# BMS-TEMPSTRIP-LEFT-S00.net
KiCad netlist of a schematic drawn in Altium Designer
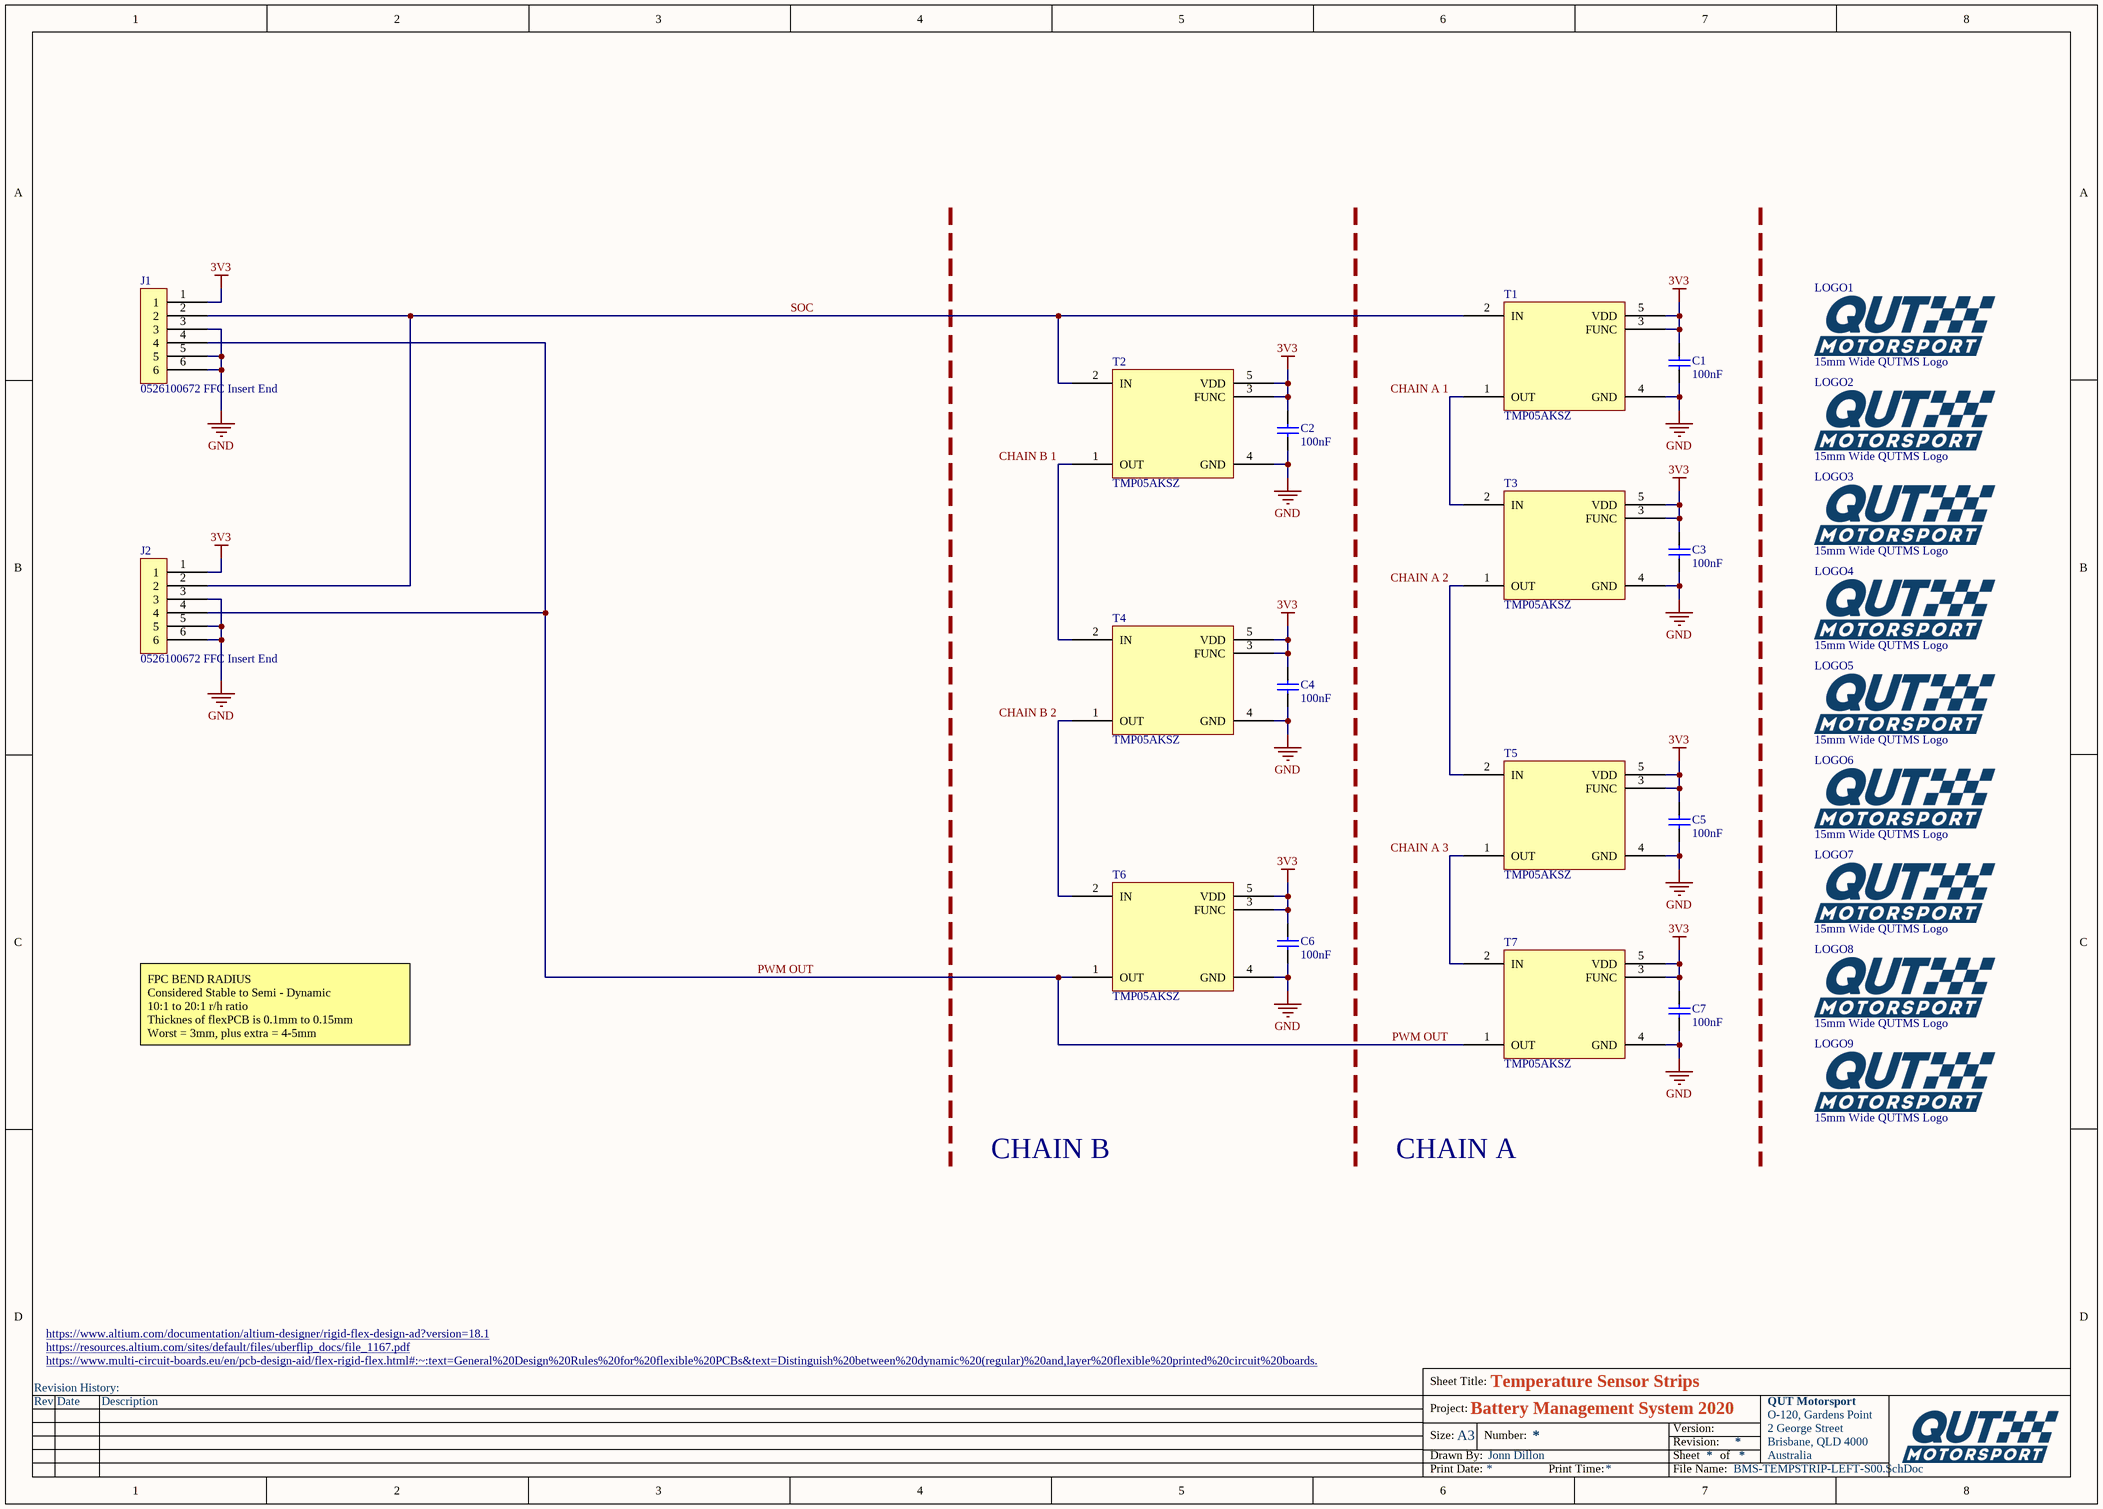
[diagram p0: BMS-TEMPSTRIP-LEFT-S00.SchDoc]

(export (version "E")
  (design (tool "Eeschema 10.0.6"))
  (components
    (comp (ref "C1")
      (value "100nF")
      (footprint "Cap_Ceramic_0603")
      (description "Capacitor, Ceramic, SMD, 100nF, 50V, 5%, X7R, 0603")
      (libsource (lib "StandardCapacitors") (part "100nF 50V 5% X7R 0603"))
    )
    (comp (ref "C2")
      (value "100nF")
      (footprint "Cap_Ceramic_0603")
      (description "Capacitor, Ceramic, SMD, 100nF, 50V, 5%, X7R, 0603")
      (libsource (lib "StandardCapacitors") (part "100nF 50V 5% X7R 0603"))
    )
    (comp (ref "C3")
      (value "100nF")
      (footprint "Cap_Ceramic_0603")
      (description "Capacitor, Ceramic, SMD, 100nF, 50V, 5%, X7R, 0603")
      (libsource (lib "StandardCapacitors") (part "100nF 50V 5% X7R 0603"))
    )
    (comp (ref "C4")
      (value "100nF")
      (footprint "Cap_Ceramic_0603")
      (description "Capacitor, Ceramic, SMD, 100nF, 50V, 5%, X7R, 0603")
      (libsource (lib "StandardCapacitors") (part "100nF 50V 5% X7R 0603"))
    )
    (comp (ref "C5")
      (value "100nF")
      (footprint "Cap_Ceramic_0603")
      (description "Capacitor, Ceramic, SMD, 100nF, 50V, 5%, X7R, 0603")
      (libsource (lib "StandardCapacitors") (part "100nF 50V 5% X7R 0603"))
    )
    (comp (ref "C6")
      (value "100nF")
      (footprint "Cap_Ceramic_0603")
      (description "Capacitor, Ceramic, SMD, 100nF, 50V, 5%, X7R, 0603")
      (libsource (lib "StandardCapacitors") (part "100nF 50V 5% X7R 0603"))
    )
    (comp (ref "C7")
      (value "100nF")
      (footprint "Cap_Ceramic_0603")
      (description "Capacitor, Ceramic, SMD, 100nF, 50V, 5%, X7R, 0603")
      (libsource (lib "StandardCapacitors") (part "100nF 50V 5% X7R 0603"))
    )
    (comp (ref "J1")
      (value "0526100672 FFC Insert End")
      (footprint "0526100672 FFC Insert End")
      (libsource (lib "BMS-TEMPSTRIP") (part "0526100672 FFC Insert End"))
    )
    (comp (ref "J2")
      (value "0526100672 FFC Insert End")
      (footprint "0526100672 FFC Insert End")
      (libsource (lib "BMS-TEMPSTRIP") (part "0526100672 FFC Insert End"))
    )
    (comp (ref "LOGO1")
      (value "15mm Wide QUTMS Logo")
      (footprint "QUTMS LOGO 15MM")
      (libsource (lib "QUTMS_PCBLibrary") (part "QUTMS Logo 15mm"))
    )
    (comp (ref "LOGO2")
      (value "15mm Wide QUTMS Logo")
      (footprint "QUTMS LOGO 15MM")
      (libsource (lib "QUTMS_PCBLibrary") (part "QUTMS Logo 15mm"))
    )
    (comp (ref "LOGO3")
      (value "15mm Wide QUTMS Logo")
      (footprint "QUTMS LOGO 15MM")
      (libsource (lib "QUTMS_PCBLibrary") (part "QUTMS Logo 15mm"))
    )
    (comp (ref "LOGO4")
      (value "15mm Wide QUTMS Logo")
      (footprint "QUTMS LOGO 15MM")
      (libsource (lib "QUTMS_PCBLibrary") (part "QUTMS Logo 15mm"))
    )
    (comp (ref "LOGO5")
      (value "15mm Wide QUTMS Logo")
      (footprint "QUTMS LOGO 15MM")
      (libsource (lib "QUTMS_PCBLibrary") (part "QUTMS Logo 15mm"))
    )
    (comp (ref "LOGO6")
      (value "15mm Wide QUTMS Logo")
      (footprint "QUTMS LOGO 15MM")
      (libsource (lib "QUTMS_PCBLibrary") (part "QUTMS Logo 15mm"))
    )
    (comp (ref "LOGO7")
      (value "15mm Wide QUTMS Logo")
      (footprint "QUTMS LOGO 15MM")
      (libsource (lib "QUTMS_PCBLibrary") (part "QUTMS Logo 15mm"))
    )
    (comp (ref "LOGO8")
      (value "15mm Wide QUTMS Logo")
      (footprint "QUTMS LOGO 15MM")
      (libsource (lib "QUTMS_PCBLibrary") (part "QUTMS Logo 15mm"))
    )
    (comp (ref "LOGO9")
      (value "15mm Wide QUTMS Logo")
      (footprint "QUTMS LOGO 15MM")
      (libsource (lib "QUTMS_PCBLibrary") (part "QUTMS Logo 15mm"))
    )
    (comp (ref "T1")
      (value "TMP05AKSZ")
      (footprint "SC-70 (KS-5)")
      (description "Temperature Sensor, SMD, 3.3V, 2%, SOT-353")
      (libsource (lib "BMS-TEMPSTRIP") (part "TMP05AKSZ"))
    )
    (comp (ref "T2")
      (value "TMP05AKSZ")
      (footprint "SC-70 (KS-5)")
      (description "Temperature Sensor, SMD, 3.3V, 2%, SOT-353")
      (libsource (lib "BMS-TEMPSTRIP") (part "TMP05AKSZ"))
    )
    (comp (ref "T3")
      (value "TMP05AKSZ")
      (footprint "SC-70 (KS-5)")
      (description "Temperature Sensor, SMD, 3.3V, 2%, SOT-353")
      (libsource (lib "BMS-TEMPSTRIP") (part "TMP05AKSZ"))
    )
    (comp (ref "T4")
      (value "TMP05AKSZ")
      (footprint "SC-70 (KS-5)")
      (description "Temperature Sensor, SMD, 3.3V, 2%, SOT-353")
      (libsource (lib "BMS-TEMPSTRIP") (part "TMP05AKSZ"))
    )
    (comp (ref "T5")
      (value "TMP05AKSZ")
      (footprint "SC-70 (KS-5)")
      (description "Temperature Sensor, SMD, 3.3V, 2%, SOT-353")
      (libsource (lib "BMS-TEMPSTRIP") (part "TMP05AKSZ"))
    )
    (comp (ref "T6")
      (value "TMP05AKSZ")
      (footprint "SC-70 (KS-5)")
      (description "Temperature Sensor, SMD, 3.3V, 2%, SOT-353")
      (libsource (lib "BMS-TEMPSTRIP") (part "TMP05AKSZ"))
    )
    (comp (ref "T7")
      (value "TMP05AKSZ")
      (footprint "SC-70 (KS-5)")
      (description "Temperature Sensor, SMD, 3.3V, 2%, SOT-353")
      (libsource (lib "BMS-TEMPSTRIP") (part "TMP05AKSZ"))
    )
  )
  (nets
    (net (code "1") (name "/CHAIN A 1") (class "Default")
      (node (ref "T1") (pin "1") (pinfunction "OUT_1") (pintype "passive"))
      (node (ref "T3") (pin "2") (pinfunction "IN_2") (pintype "passive"))
    )
    (net (code "2") (name "/CHAIN A 2") (class "Default")
      (node (ref "T3") (pin "1") (pinfunction "OUT_1") (pintype "passive"))
      (node (ref "T5") (pin "2") (pinfunction "IN_2") (pintype "passive"))
    )
    (net (code "3") (name "/CHAIN A 3") (class "Default")
      (node (ref "T5") (pin "1") (pinfunction "OUT_1") (pintype "passive"))
      (node (ref "T7") (pin "2") (pinfunction "IN_2") (pintype "passive"))
    )
    (net (code "4") (name "/CHAIN B 1") (class "Default")
      (node (ref "T2") (pin "1") (pinfunction "OUT_1") (pintype "passive"))
      (node (ref "T4") (pin "2") (pinfunction "IN_2") (pintype "passive"))
    )
    (net (code "5") (name "/CHAIN B 2") (class "Default")
      (node (ref "T4") (pin "1") (pinfunction "OUT_1") (pintype "passive"))
      (node (ref "T6") (pin "2") (pinfunction "IN_2") (pintype "passive"))
    )
    (net (code "6") (name "/PWM OUT") (class "Default")
      (node (ref "J1") (pin "4") (pinfunction "4_4") (pintype "passive"))
      (node (ref "J2") (pin "4") (pinfunction "4_4") (pintype "passive"))
      (node (ref "T6") (pin "1") (pinfunction "OUT_1") (pintype "passive"))
      (node (ref "T7") (pin "1") (pinfunction "OUT_1") (pintype "passive"))
    )
    (net (code "7") (name "/SOC") (class "Default")
      (node (ref "J1") (pin "2") (pinfunction "2_2") (pintype "passive"))
      (node (ref "J2") (pin "2") (pinfunction "2_2") (pintype "passive"))
      (node (ref "T1") (pin "2") (pinfunction "IN_2") (pintype "passive"))
      (node (ref "T2") (pin "2") (pinfunction "IN_2") (pintype "passive"))
    )
    (net (code "8") (name "3V3") (class "Default")
      (node (ref "C1") (pin "1") (pinfunction "1_1") (pintype "passive"))
      (node (ref "C2") (pin "1") (pinfunction "1_1") (pintype "passive"))
      (node (ref "C3") (pin "1") (pinfunction "1_1") (pintype "passive"))
      (node (ref "C4") (pin "1") (pinfunction "1_1") (pintype "passive"))
      (node (ref "C5") (pin "1") (pinfunction "1_1") (pintype "passive"))
      (node (ref "C6") (pin "1") (pinfunction "1_1") (pintype "passive"))
      (node (ref "C7") (pin "1") (pinfunction "1_1") (pintype "passive"))
      (node (ref "J1") (pin "1") (pinfunction "1_1") (pintype "passive"))
      (node (ref "J2") (pin "1") (pinfunction "1_1") (pintype "passive"))
      (node (ref "T1") (pin "3") (pinfunction "FUNC_3") (pintype "passive"))
      (node (ref "T1") (pin "5") (pinfunction "VDD_5") (pintype "passive"))
      (node (ref "T2") (pin "3") (pinfunction "FUNC_3") (pintype "passive"))
      (node (ref "T2") (pin "5") (pinfunction "VDD_5") (pintype "passive"))
      (node (ref "T3") (pin "3") (pinfunction "FUNC_3") (pintype "passive"))
      (node (ref "T3") (pin "5") (pinfunction "VDD_5") (pintype "passive"))
      (node (ref "T4") (pin "3") (pinfunction "FUNC_3") (pintype "passive"))
      (node (ref "T4") (pin "5") (pinfunction "VDD_5") (pintype "passive"))
      (node (ref "T5") (pin "3") (pinfunction "FUNC_3") (pintype "passive"))
      (node (ref "T5") (pin "5") (pinfunction "VDD_5") (pintype "passive"))
      (node (ref "T6") (pin "3") (pinfunction "FUNC_3") (pintype "passive"))
      (node (ref "T6") (pin "5") (pinfunction "VDD_5") (pintype "passive"))
      (node (ref "T7") (pin "3") (pinfunction "FUNC_3") (pintype "passive"))
      (node (ref "T7") (pin "5") (pinfunction "VDD_5") (pintype "passive"))
    )
    (net (code "9") (name "GND") (class "Default")
      (node (ref "C1") (pin "2") (pinfunction "2_2") (pintype "passive"))
      (node (ref "C2") (pin "2") (pinfunction "2_2") (pintype "passive"))
      (node (ref "C3") (pin "2") (pinfunction "2_2") (pintype "passive"))
      (node (ref "C4") (pin "2") (pinfunction "2_2") (pintype "passive"))
      (node (ref "C5") (pin "2") (pinfunction "2_2") (pintype "passive"))
      (node (ref "C6") (pin "2") (pinfunction "2_2") (pintype "passive"))
      (node (ref "C7") (pin "2") (pinfunction "2_2") (pintype "passive"))
      (node (ref "J1") (pin "3") (pinfunction "3_3") (pintype "passive"))
      (node (ref "J1") (pin "5") (pinfunction "5_5") (pintype "passive"))
      (node (ref "J1") (pin "6") (pinfunction "6_6") (pintype "passive"))
      (node (ref "J2") (pin "3") (pinfunction "3_3") (pintype "passive"))
      (node (ref "J2") (pin "5") (pinfunction "5_5") (pintype "passive"))
      (node (ref "J2") (pin "6") (pinfunction "6_6") (pintype "passive"))
      (node (ref "T1") (pin "4") (pinfunction "GND_4") (pintype "passive"))
      (node (ref "T2") (pin "4") (pinfunction "GND_4") (pintype "passive"))
      (node (ref "T3") (pin "4") (pinfunction "GND_4") (pintype "passive"))
      (node (ref "T4") (pin "4") (pinfunction "GND_4") (pintype "passive"))
      (node (ref "T5") (pin "4") (pinfunction "GND_4") (pintype "passive"))
      (node (ref "T6") (pin "4") (pinfunction "GND_4") (pintype "passive"))
      (node (ref "T7") (pin "4") (pinfunction "GND_4") (pintype "passive"))
    )
  )
)
